# FPGA_Memory.net
KiCad netlist of a schematic drawn in Altium Designer
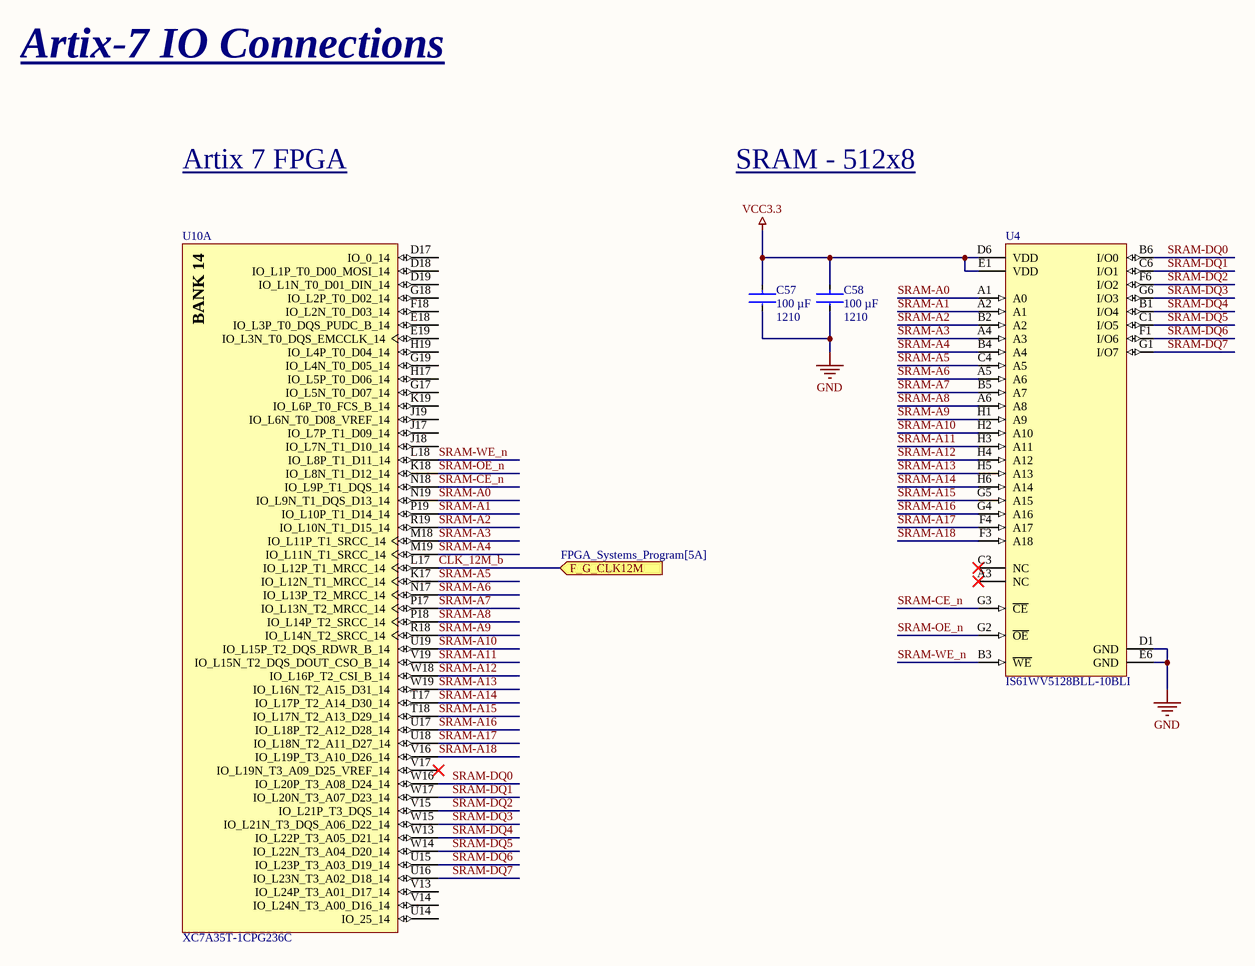
[diagram p0: FPGA_Memory.SchDoc]

(export (version "E")
  (design (tool "Eeschema 10.0.6"))
  (components
    (comp (ref "C57")
      (value "CL32A107MQVNNNE")
      (footprint "FP-CL32-IPC_C")
      (description "CAP CER 100UF 6.3V X5R 1210")
      (fields
        (field (name "VOLTAGE") "6.3V")
        (field (name "TOLERANCE") "20%")
        (field (name "CASE CODE (IMPERIAL)") "1210")
        (field (name "CAPACITANCE") "100 µF")
      )
      (libsource (lib "Altium Content Vault") (part "b4654b650e69147ec39a6b967a45e02"))
    )
    (comp (ref "C58")
      (value "CL32A107MQVNNNE")
      (footprint "FP-CL32-IPC_C")
      (description "CAP CER 100UF 6.3V X5R 1210")
      (fields
        (field (name "VOLTAGE") "6.3V")
        (field (name "TOLERANCE") "20%")
        (field (name "CASE CODE (IMPERIAL)") "1210")
        (field (name "CAPACITANCE") "100 µF")
      )
      (libsource (lib "Altium Content Vault") (part "b4654b650e69147ec39a6b967a45e02"))
    )
    (comp (ref "U4")
      (value "IS61WV5128BLL-10BLI")
      (footprint "FP-IS61WV5128BLL-10BLI-IPC_A")
      (libsource (lib "Altium Content Vault") (part "7547a2fdd47ed936ab9e56fa022b1f9"))
    )
    (comp (ref "U10")
      (value "XC7A35T-1CPG236C")
      (footprint "CPG236")
      (description "Artix-7 FPGA, 106 User I/Os, 2 GTP, 238-Ball BGA, Speed Grade 1, Commercial Grade, Pb-Free")
      (fields (field (name "MANUFACTURER") "Xilinx"))
      (libsource (lib "Altium Content Vault") (part "XLNX-XC7A35T-CPG236"))
    )
  )
  (nets
    (net (code "1") (name "/CLK_12M_b") (class "Default")
      (node (ref "U10") (pin "L17") (pinfunction "IO_L12P_T1_MRCC_14_L17") (pintype "bidirectional"))
    )
    (net (code "2") (name "/SRAM-A0") (class "Default")
      (node (ref "U10") (pin "N19") (pinfunction "IO_L9N_T1_DQS_D13_14_N19") (pintype "bidirectional"))
      (node (ref "U4") (pin "A1") (pinfunction "A0_A1") (pintype "input"))
    )
    (net (code "3") (name "/SRAM-A1") (class "Default")
      (node (ref "U10") (pin "P19") (pinfunction "IO_L10P_T1_D14_14_P19") (pintype "bidirectional"))
      (node (ref "U4") (pin "A2") (pinfunction "A1_A2") (pintype "input"))
    )
    (net (code "4") (name "/SRAM-A2") (class "Default")
      (node (ref "U10") (pin "R19") (pinfunction "IO_L10N_T1_D15_14_R19") (pintype "bidirectional"))
      (node (ref "U4") (pin "B2") (pinfunction "A2_B2") (pintype "input"))
    )
    (net (code "5") (name "/SRAM-A3") (class "Default")
      (node (ref "U10") (pin "M18") (pinfunction "IO_L11P_T1_SRCC_14_M18") (pintype "bidirectional"))
      (node (ref "U4") (pin "A4") (pinfunction "A3_A4") (pintype "input"))
    )
    (net (code "6") (name "/SRAM-A4") (class "Default")
      (node (ref "U10") (pin "M19") (pinfunction "IO_L11N_T1_SRCC_14_M19") (pintype "bidirectional"))
      (node (ref "U4") (pin "B4") (pinfunction "A4_B4") (pintype "input"))
    )
    (net (code "7") (name "/SRAM-A5") (class "Default")
      (node (ref "U10") (pin "K17") (pinfunction "IO_L12N_T1_MRCC_14_K17") (pintype "bidirectional"))
      (node (ref "U4") (pin "C4") (pinfunction "A5_C4") (pintype "input"))
    )
    (net (code "8") (name "/SRAM-A6") (class "Default")
      (node (ref "U10") (pin "N17") (pinfunction "IO_L13P_T2_MRCC_14_N17") (pintype "bidirectional"))
      (node (ref "U4") (pin "A5") (pinfunction "A6_A5") (pintype "input"))
    )
    (net (code "9") (name "/SRAM-A7") (class "Default")
      (node (ref "U10") (pin "P17") (pinfunction "IO_L13N_T2_MRCC_14_P17") (pintype "bidirectional"))
      (node (ref "U4") (pin "B5") (pinfunction "A7_B5") (pintype "input"))
    )
    (net (code "10") (name "/SRAM-A8") (class "Default")
      (node (ref "U10") (pin "P18") (pinfunction "IO_L14P_T2_SRCC_14_P18") (pintype "bidirectional"))
      (node (ref "U4") (pin "A6") (pinfunction "A8_A6") (pintype "input"))
    )
    (net (code "11") (name "/SRAM-A9") (class "Default")
      (node (ref "U10") (pin "R18") (pinfunction "IO_L14N_T2_SRCC_14_R18") (pintype "bidirectional"))
      (node (ref "U4") (pin "H1") (pinfunction "A9_H1") (pintype "input"))
    )
    (net (code "12") (name "/SRAM-A10") (class "Default")
      (node (ref "U10") (pin "U19") (pinfunction "IO_L15P_T2_DQS_RDWR_B_14_U19") (pintype "bidirectional"))
      (node (ref "U4") (pin "H2") (pinfunction "A10_H2") (pintype "input"))
    )
    (net (code "13") (name "/SRAM-A11") (class "Default")
      (node (ref "U10") (pin "V19") (pinfunction "IO_L15N_T2_DQS_DOUT_CSO_B_14_V19") (pintype "bidirectional"))
      (node (ref "U4") (pin "H3") (pinfunction "A11_H3") (pintype "input"))
    )
    (net (code "14") (name "/SRAM-A12") (class "Default")
      (node (ref "U10") (pin "W18") (pinfunction "IO_L16P_T2_CSI_B_14_W18") (pintype "bidirectional"))
      (node (ref "U4") (pin "H4") (pinfunction "A12_H4") (pintype "input"))
    )
    (net (code "15") (name "/SRAM-A13") (class "Default")
      (node (ref "U10") (pin "W19") (pinfunction "IO_L16N_T2_A15_D31_14_W19") (pintype "bidirectional"))
      (node (ref "U4") (pin "H5") (pinfunction "A13_H5") (pintype "input"))
    )
    (net (code "16") (name "/SRAM-A14") (class "Default")
      (node (ref "U10") (pin "T17") (pinfunction "IO_L17P_T2_A14_D30_14_T17") (pintype "bidirectional"))
      (node (ref "U4") (pin "H6") (pinfunction "A14_H6") (pintype "input"))
    )
    (net (code "17") (name "/SRAM-A15") (class "Default")
      (node (ref "U10") (pin "T18") (pinfunction "IO_L17N_T2_A13_D29_14_T18") (pintype "bidirectional"))
      (node (ref "U4") (pin "G5") (pinfunction "A15_G5") (pintype "input"))
    )
    (net (code "18") (name "/SRAM-A16") (class "Default")
      (node (ref "U10") (pin "U17") (pinfunction "IO_L18P_T2_A12_D28_14_U17") (pintype "bidirectional"))
      (node (ref "U4") (pin "G4") (pinfunction "A16_G4") (pintype "input"))
    )
    (net (code "19") (name "/SRAM-A17") (class "Default")
      (node (ref "U10") (pin "U18") (pinfunction "IO_L18N_T2_A11_D27_14_U18") (pintype "bidirectional"))
      (node (ref "U4") (pin "F4") (pinfunction "A17_F4") (pintype "input"))
    )
    (net (code "20") (name "/SRAM-A18") (class "Default")
      (node (ref "U10") (pin "V16") (pinfunction "IO_L19P_T3_A10_D26_14_V16") (pintype "bidirectional"))
      (node (ref "U4") (pin "F3") (pinfunction "A18_F3") (pintype "input"))
    )
    (net (code "21") (name "/SRAM-CE_n") (class "Default")
      (node (ref "U10") (pin "N18") (pinfunction "IO_L9P_T1_DQS_14_N18") (pintype "bidirectional"))
      (node (ref "U4") (pin "G3") (pinfunction "~{CE}_G3") (pintype "input"))
    )
    (net (code "22") (name "/SRAM-DQ0") (class "Default")
      (node (ref "U10") (pin "W16") (pinfunction "IO_L20P_T3_A08_D24_14_W16") (pintype "bidirectional"))
      (node (ref "U4") (pin "B6") (pinfunction "I/O0_B6") (pintype "bidirectional"))
    )
    (net (code "23") (name "/SRAM-DQ1") (class "Default")
      (node (ref "U10") (pin "W17") (pinfunction "IO_L20N_T3_A07_D23_14_W17") (pintype "bidirectional"))
      (node (ref "U4") (pin "C6") (pinfunction "I/O1_C6") (pintype "bidirectional"))
    )
    (net (code "24") (name "/SRAM-DQ2") (class "Default")
      (node (ref "U10") (pin "V15") (pinfunction "IO_L21P_T3_DQS_14_V15") (pintype "bidirectional"))
      (node (ref "U4") (pin "F6") (pinfunction "I/O2_F6") (pintype "bidirectional"))
    )
    (net (code "25") (name "/SRAM-DQ3") (class "Default")
      (node (ref "U10") (pin "W15") (pinfunction "IO_L21N_T3_DQS_A06_D22_14_W15") (pintype "bidirectional"))
      (node (ref "U4") (pin "G6") (pinfunction "I/O3_G6") (pintype "bidirectional"))
    )
    (net (code "26") (name "/SRAM-DQ4") (class "Default")
      (node (ref "U10") (pin "W13") (pinfunction "IO_L22P_T3_A05_D21_14_W13") (pintype "bidirectional"))
      (node (ref "U4") (pin "B1") (pinfunction "I/O4_B1") (pintype "bidirectional"))
    )
    (net (code "27") (name "/SRAM-DQ5") (class "Default")
      (node (ref "U10") (pin "W14") (pinfunction "IO_L22N_T3_A04_D20_14_W14") (pintype "bidirectional"))
      (node (ref "U4") (pin "C1") (pinfunction "I/O5_C1") (pintype "bidirectional"))
    )
    (net (code "28") (name "/SRAM-DQ6") (class "Default")
      (node (ref "U10") (pin "U15") (pinfunction "IO_L23P_T3_A03_D19_14_U15") (pintype "bidirectional"))
      (node (ref "U4") (pin "F1") (pinfunction "I/O6_F1") (pintype "bidirectional"))
    )
    (net (code "29") (name "/SRAM-DQ7") (class "Default")
      (node (ref "U10") (pin "U16") (pinfunction "IO_L23N_T3_A02_D18_14_U16") (pintype "bidirectional"))
      (node (ref "U4") (pin "G1") (pinfunction "I/O7_G1") (pintype "bidirectional"))
    )
    (net (code "30") (name "/SRAM-OE_n") (class "Default")
      (node (ref "U10") (pin "K18") (pinfunction "IO_L8N_T1_D12_14_K18") (pintype "bidirectional"))
      (node (ref "U4") (pin "G2") (pinfunction "~{OE}_G2") (pintype "input"))
    )
    (net (code "31") (name "/SRAM-WE_n") (class "Default")
      (node (ref "U10") (pin "L18") (pinfunction "IO_L8P_T1_D11_14_L18") (pintype "bidirectional"))
      (node (ref "U4") (pin "B3") (pinfunction "~{WE}_B3") (pintype "input"))
    )
    (net (code "32") (name "GND") (class "Default")
      (node (ref "C57") (pin "2") (pinfunction "2_2") (pintype "passive"))
      (node (ref "C58") (pin "2") (pinfunction "2_2") (pintype "passive"))
      (node (ref "U4") (pin "D1") (pinfunction "GND_D1") (pintype "power_in"))
      (node (ref "U4") (pin "E6") (pinfunction "GND_E6") (pintype "power_in"))
    )
    (net (code "33") (name "VCC3.3") (class "Default")
      (node (ref "C57") (pin "1") (pinfunction "1_1") (pintype "passive"))
      (node (ref "C58") (pin "1") (pinfunction "1_1") (pintype "passive"))
      (node (ref "U4") (pin "D6") (pinfunction "VDD_D6") (pintype "power_in"))
      (node (ref "U4") (pin "E1") (pinfunction "VDD_E1") (pintype "power_in"))
    )
    (net (code "34") (name "unconnected-(U4-NC-PadA3)") (class "Default")
      (node (ref "U4") (pin "A3") (pinfunction "NC_A3") (pintype "passive+no_connect"))
    )
    (net (code "35") (name "unconnected-(U4-NC-PadC3)") (class "Default")
      (node (ref "U4") (pin "C3") (pinfunction "NC_C3") (pintype "passive+no_connect"))
    )
    (net (code "36") (name "unconnected-(U10A-IO_0_14-PadD17)") (class "Default")
      (node (ref "U10") (pin "D17") (pinfunction "IO_0_14_D17") (pintype "bidirectional"))
    )
    (net (code "37") (name "unconnected-(U10A-IO_25_14-PadU14)") (class "Default")
      (node (ref "U10") (pin "U14") (pinfunction "IO_25_14_U14") (pintype "bidirectional"))
    )
    (net (code "38") (name "unconnected-(U10A-IO_L1N_T0_D01_DIN_14-PadD19)") (class "Default")
      (node (ref "U10") (pin "D19") (pinfunction "IO_L1N_T0_D01_DIN_14_D19") (pintype "bidirectional"))
    )
    (net (code "39") (name "unconnected-(U10A-IO_L1P_T0_D00_MOSI_14-PadD18)") (class "Default")
      (node (ref "U10") (pin "D18") (pinfunction "IO_L1P_T0_D00_MOSI_14_D18") (pintype "bidirectional"))
    )
    (net (code "40") (name "unconnected-(U10A-IO_L2N_T0_D03_14-PadF18)") (class "Default")
      (node (ref "U10") (pin "F18") (pinfunction "IO_L2N_T0_D03_14_F18") (pintype "bidirectional"))
    )
    (net (code "41") (name "unconnected-(U10A-IO_L2P_T0_D02_14-PadG18)") (class "Default")
      (node (ref "U10") (pin "G18") (pinfunction "IO_L2P_T0_D02_14_G18") (pintype "bidirectional"))
    )
    (net (code "42") (name "unconnected-(U10A-IO_L3N_T0_DQS_EMCCLK_14-PadE19)") (class "Default")
      (node (ref "U10") (pin "E19") (pinfunction "IO_L3N_T0_DQS_EMCCLK_14_E19") (pintype "bidirectional"))
    )
    (net (code "43") (name "unconnected-(U10A-IO_L3P_T0_DQS_PUDC_B_14-PadE18)") (class "Default")
      (node (ref "U10") (pin "E18") (pinfunction "IO_L3P_T0_DQS_PUDC_B_14_E18") (pintype "bidirectional"))
    )
    (net (code "44") (name "unconnected-(U10A-IO_L4N_T0_D05_14-PadG19)") (class "Default")
      (node (ref "U10") (pin "G19") (pinfunction "IO_L4N_T0_D05_14_G19") (pintype "bidirectional"))
    )
    (net (code "45") (name "unconnected-(U10A-IO_L4P_T0_D04_14-PadH19)") (class "Default")
      (node (ref "U10") (pin "H19") (pinfunction "IO_L4P_T0_D04_14_H19") (pintype "bidirectional"))
    )
    (net (code "46") (name "unconnected-(U10A-IO_L5N_T0_D07_14-PadG17)") (class "Default")
      (node (ref "U10") (pin "G17") (pinfunction "IO_L5N_T0_D07_14_G17") (pintype "bidirectional"))
    )
    (net (code "47") (name "unconnected-(U10A-IO_L5P_T0_D06_14-PadH17)") (class "Default")
      (node (ref "U10") (pin "H17") (pinfunction "IO_L5P_T0_D06_14_H17") (pintype "bidirectional"))
    )
    (net (code "48") (name "unconnected-(U10A-IO_L6N_T0_D08_VREF_14-PadJ19)") (class "Default")
      (node (ref "U10") (pin "J19") (pinfunction "IO_L6N_T0_D08_VREF_14_J19") (pintype "bidirectional"))
    )
    (net (code "49") (name "unconnected-(U10A-IO_L6P_T0_FCS_B_14-PadK19)") (class "Default")
      (node (ref "U10") (pin "K19") (pinfunction "IO_L6P_T0_FCS_B_14_K19") (pintype "bidirectional"))
    )
    (net (code "50") (name "unconnected-(U10A-IO_L7N_T1_D10_14-PadJ18)") (class "Default")
      (node (ref "U10") (pin "J18") (pinfunction "IO_L7N_T1_D10_14_J18") (pintype "bidirectional"))
    )
    (net (code "51") (name "unconnected-(U10A-IO_L7P_T1_D09_14-PadJ17)") (class "Default")
      (node (ref "U10") (pin "J17") (pinfunction "IO_L7P_T1_D09_14_J17") (pintype "bidirectional"))
    )
    (net (code "52") (name "unconnected-(U10A-IO_L19N_T3_A09_D25_VREF_14-PadV17)") (class "Default")
      (node (ref "U10") (pin "V17") (pinfunction "IO_L19N_T3_A09_D25_VREF_14_V17") (pintype "bidirectional+no_connect"))
    )
    (net (code "53") (name "unconnected-(U10A-IO_L24N_T3_A00_D16_14-PadV14)") (class "Default")
      (node (ref "U10") (pin "V14") (pinfunction "IO_L24N_T3_A00_D16_14_V14") (pintype "bidirectional"))
    )
    (net (code "54") (name "unconnected-(U10A-IO_L24P_T3_A01_D17_14-PadV13)") (class "Default")
      (node (ref "U10") (pin "V13") (pinfunction "IO_L24P_T3_A01_D17_14_V13") (pintype "bidirectional"))
    )
  )
)
